# ThumbJoyStick.net
KiCad netlist of a schematic drawn in EAGLE
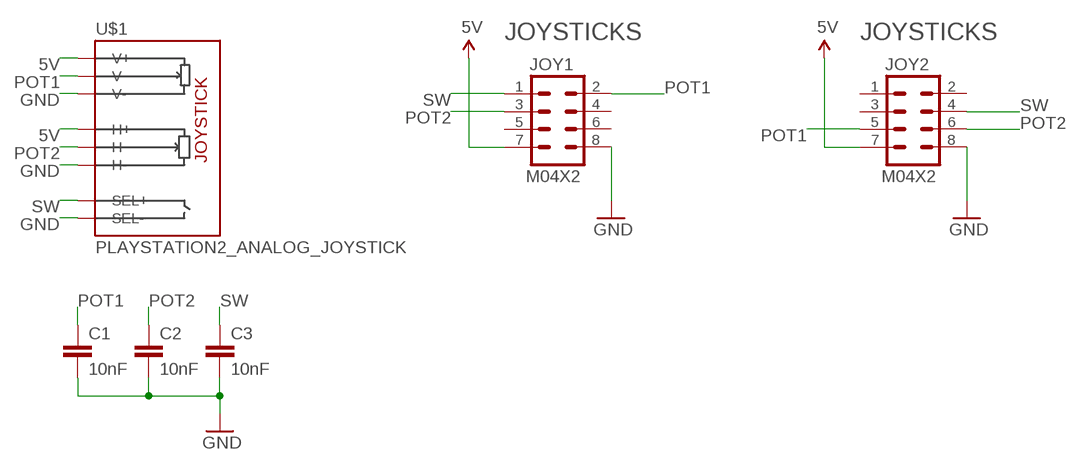
[diagram p0: schematic, sheet 1]

(export (version "E")
  (design (tool "Eeschema 10.0.6"))
  (components
    (comp (ref "C1")
      (value "10nF")
      (footprint "eagle-import:0603-CAP")
      (libsource (lib "eagle-import") (part "CAP0603-CAP"))
    )
    (comp (ref "C2")
      (value "10nF")
      (footprint "eagle-import:0603-CAP")
      (libsource (lib "eagle-import") (part "CAP0603-CAP"))
    )
    (comp (ref "C3")
      (value "10nF")
      (footprint "eagle-import:0603-CAP")
      (libsource (lib "eagle-import") (part "CAP0603-CAP"))
    )
    (comp (ref "JOY1")
      (value "M04X2")
      (footprint "eagle-import:2X4")
      (libsource (lib "eagle-import") (part "M04X2"))
    )
    (comp (ref "JOY2")
      (value "M04X2")
      (footprint "eagle-import:2X4")
      (libsource (lib "eagle-import") (part "M04X2"))
    )
    (comp (ref "U$1")
      (value "PLAYSTATION2_ANALOG_JOYSTICK")
      (footprint "eagle-import:PLAYSTATION2_ANALOG_JOYSTICK")
      (libsource (lib "eagle-import") (part "PLAYSTATION2_ANALOG_JOYSTICK"))
    )
  )
  (nets
    (net (code "1") (name "/POT1") (class "Default")
      (node (ref "C1") (pin "1") (pinfunction "1_1") (pintype "passive"))
      (node (ref "JOY1") (pin "2") (pinfunction "2_2") (pintype "passive"))
      (node (ref "JOY2") (pin "5") (pinfunction "5_5") (pintype "passive"))
      (node (ref "U$1") (pin "V2") (pinfunction "V_V2") (pintype "bidirectional"))
    )
    (net (code "2") (name "/POT2") (class "Default")
      (node (ref "C2") (pin "1") (pinfunction "1_1") (pintype "passive"))
      (node (ref "JOY1") (pin "3") (pinfunction "3_3") (pintype "passive"))
      (node (ref "JOY2") (pin "6") (pinfunction "6_6") (pintype "passive"))
      (node (ref "U$1") (pin "H2") (pinfunction "H_H2") (pintype "bidirectional"))
    )
    (net (code "3") (name "/SW") (class "Default")
      (node (ref "C3") (pin "1") (pinfunction "1_1") (pintype "passive"))
      (node (ref "JOY1") (pin "1") (pinfunction "1_1") (pintype "passive"))
      (node (ref "JOY2") (pin "4") (pinfunction "4_4") (pintype "passive"))
      (node (ref "U$1") (pin "B1A") (pinfunction "SEL+_B1A") (pintype "bidirectional"))
    )
    (net (code "4") (name "5V") (class "Default")
      (node (ref "JOY1") (pin "7") (pinfunction "7_7") (pintype "passive"))
      (node (ref "JOY2") (pin "7") (pinfunction "7_7") (pintype "passive"))
      (node (ref "U$1") (pin "H1") (pinfunction "H+_H1") (pintype "bidirectional"))
      (node (ref "U$1") (pin "V1") (pinfunction "V+_V1") (pintype "bidirectional"))
    )
    (net (code "5") (name "GND") (class "Default")
      (node (ref "C1") (pin "2") (pinfunction "2_2") (pintype "passive"))
      (node (ref "C2") (pin "2") (pinfunction "2_2") (pintype "passive"))
      (node (ref "C3") (pin "2") (pinfunction "2_2") (pintype "passive"))
      (node (ref "JOY1") (pin "8") (pinfunction "8_8") (pintype "passive"))
      (node (ref "JOY2") (pin "8") (pinfunction "8_8") (pintype "passive"))
      (node (ref "U$1") (pin "B2A") (pinfunction "SEL-_B2A") (pintype "bidirectional"))
      (node (ref "U$1") (pin "H3") (pinfunction "H-_H3") (pintype "bidirectional"))
      (node (ref "U$1") (pin "V3") (pinfunction "V-_V3") (pintype "bidirectional"))
    )
    (net (code "6") (name "unconnected-(JOY1-Pad4)") (class "Default")
      (node (ref "JOY1") (pin "4") (pinfunction "4_4") (pintype "passive"))
    )
    (net (code "7") (name "unconnected-(JOY1-Pad5)") (class "Default")
      (node (ref "JOY1") (pin "5") (pinfunction "5_5") (pintype "passive"))
    )
    (net (code "8") (name "unconnected-(JOY1-Pad6)") (class "Default")
      (node (ref "JOY1") (pin "6") (pinfunction "6_6") (pintype "passive"))
    )
    (net (code "9") (name "unconnected-(JOY2-Pad1)") (class "Default")
      (node (ref "JOY2") (pin "1") (pinfunction "1_1") (pintype "passive"))
    )
    (net (code "10") (name "unconnected-(JOY2-Pad2)") (class "Default")
      (node (ref "JOY2") (pin "2") (pinfunction "2_2") (pintype "passive"))
    )
    (net (code "11") (name "unconnected-(JOY2-Pad3)") (class "Default")
      (node (ref "JOY2") (pin "3") (pinfunction "3_3") (pintype "passive"))
    )
  )
)
